# B611B.net
KiCad netlist of a schematic drawn in EAGLE
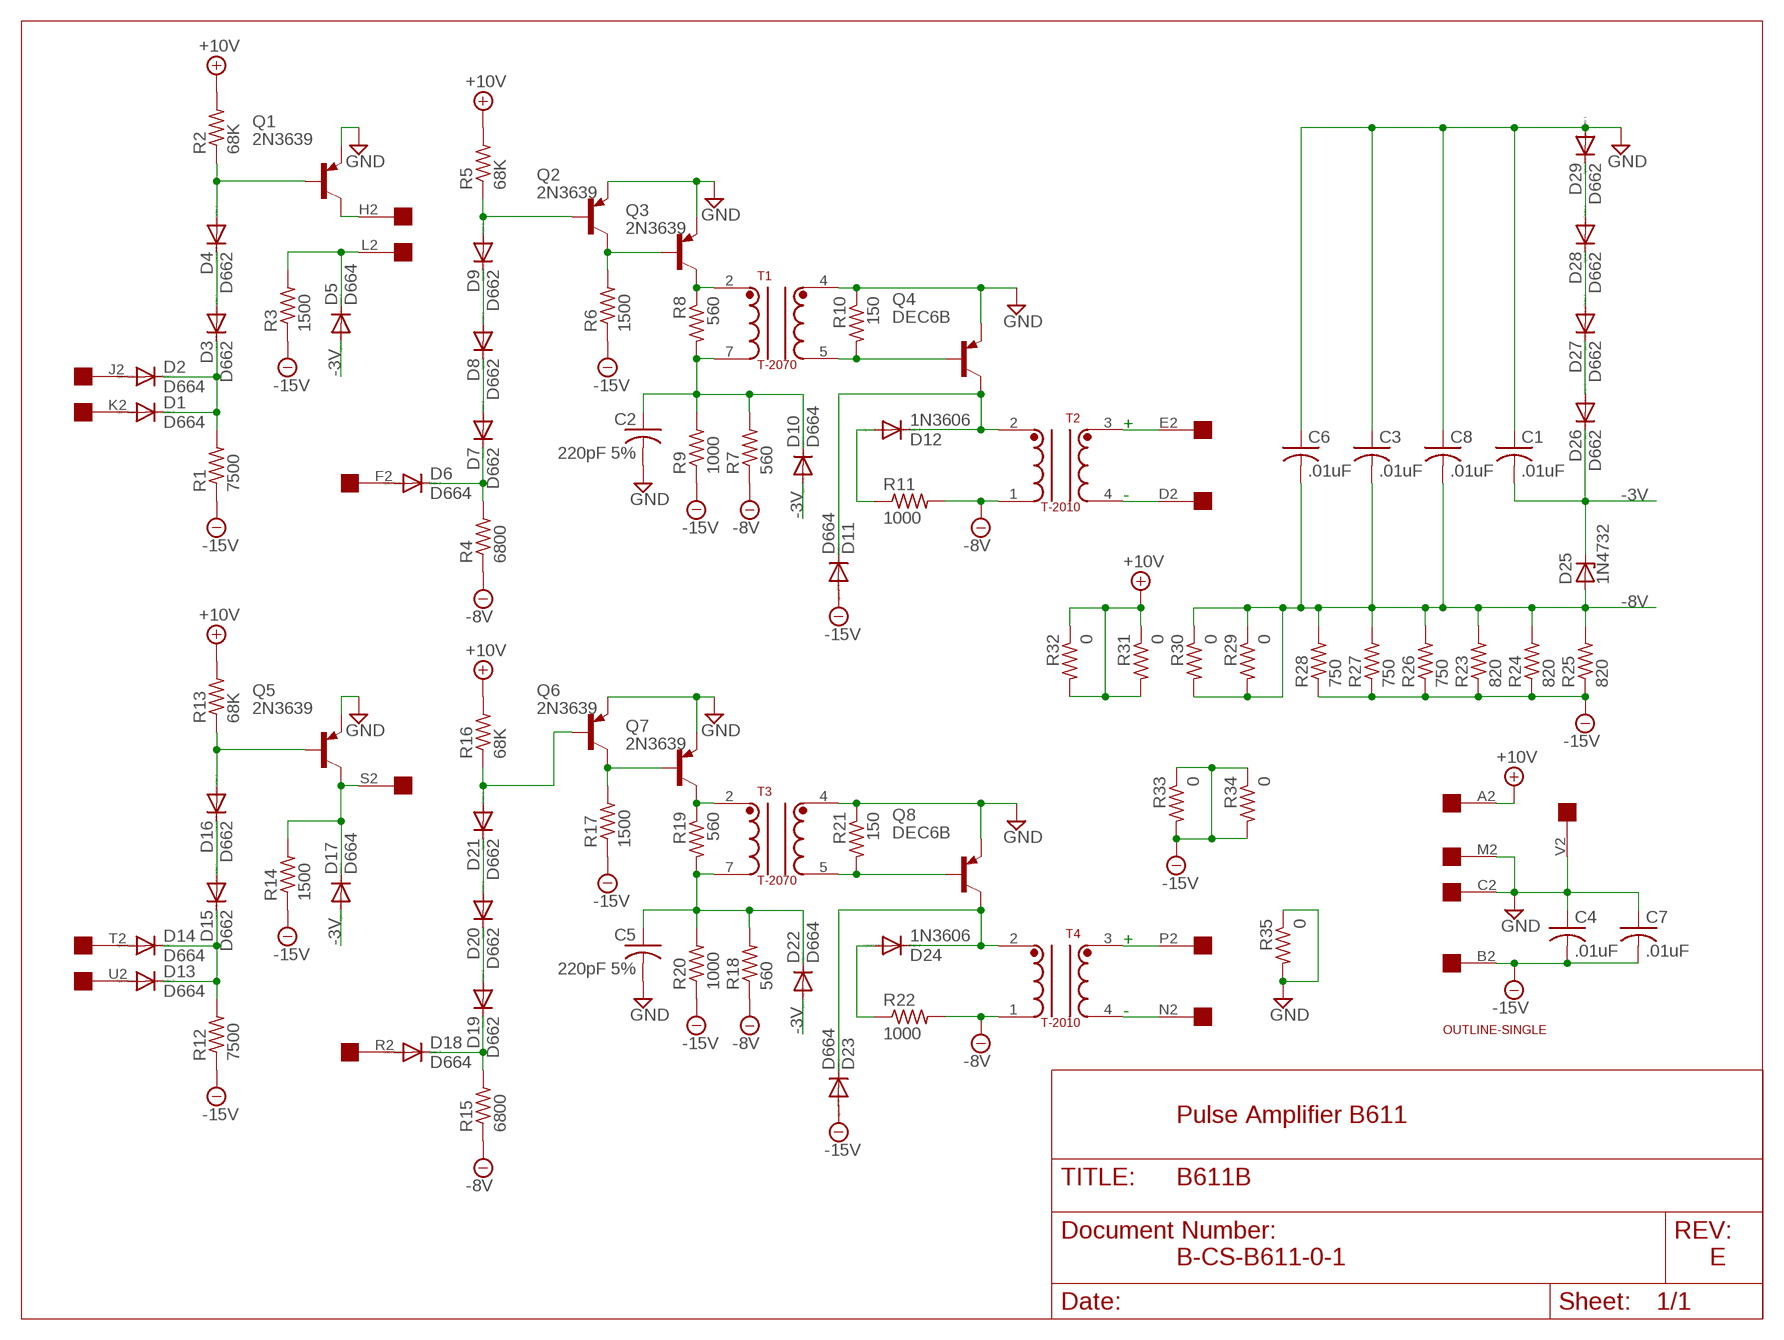
[diagram p0: schematic, sheet 1]

(export (version "E")
  (design (tool "Eeschema 10.0.6"))
  (components
    (comp (ref "C1")
      (value ".01uF")
      (footprint "eagle-import:C063-025X075")
      (libsource (lib "eagle-import") (part "C-US"))
    )
    (comp (ref "C2")
      (value "220pF 5%")
      (footprint "eagle-import:C150-054X183")
      (libsource (lib "eagle-import") (part "C-US150-054X183"))
    )
    (comp (ref "C3")
      (value ".01uF")
      (footprint "eagle-import:C063-025X075")
      (libsource (lib "eagle-import") (part "C-US"))
    )
    (comp (ref "C4")
      (value ".01uF")
      (footprint "eagle-import:C063-025X075")
      (libsource (lib "eagle-import") (part "C-US"))
    )
    (comp (ref "C5")
      (value "220pF 5%")
      (footprint "eagle-import:C150-054X183")
      (libsource (lib "eagle-import") (part "C-US150-054X183"))
    )
    (comp (ref "C6")
      (value ".01uF")
      (footprint "eagle-import:C063-025X075")
      (libsource (lib "eagle-import") (part "C-US"))
    )
    (comp (ref "C7")
      (value ".01uF")
      (footprint "eagle-import:C063-025X075")
      (libsource (lib "eagle-import") (part "C-US"))
    )
    (comp (ref "C8")
      (value ".01uF")
      (footprint "eagle-import:C063-025X075")
      (libsource (lib "eagle-import") (part "C-US"))
    )
    (comp (ref "D1")
      (value "D664")
      (footprint "eagle-import:DO35-10")
      (libsource (lib "eagle-import") (part "1N4148DO35-10"))
    )
    (comp (ref "D2")
      (value "D664")
      (footprint "eagle-import:DO35-10")
      (libsource (lib "eagle-import") (part "1N4148DO35-10"))
    )
    (comp (ref "D3")
      (value "D662")
      (footprint "eagle-import:DO35-10")
      (libsource (lib "eagle-import") (part "1N4148DO35-10"))
    )
    (comp (ref "D4")
      (value "D662")
      (footprint "eagle-import:DO35-10")
      (libsource (lib "eagle-import") (part "1N4148DO35-10"))
    )
    (comp (ref "D5")
      (value "D664")
      (footprint "eagle-import:DO35-10")
      (libsource (lib "eagle-import") (part "1N4148DO35-10"))
    )
    (comp (ref "D6")
      (value "D664")
      (footprint "eagle-import:DO35-10")
      (libsource (lib "eagle-import") (part "1N4148DO35-10"))
    )
    (comp (ref "D7")
      (value "D662")
      (footprint "eagle-import:DO35-10")
      (libsource (lib "eagle-import") (part "1N4148DO35-10"))
    )
    (comp (ref "D8")
      (value "D662")
      (footprint "eagle-import:DO35-10")
      (libsource (lib "eagle-import") (part "1N4148DO35-10"))
    )
    (comp (ref "D9")
      (value "D662")
      (footprint "eagle-import:DO35-10")
      (libsource (lib "eagle-import") (part "1N4148DO35-10"))
    )
    (comp (ref "D10")
      (value "D664")
      (footprint "eagle-import:DO35-10")
      (libsource (lib "eagle-import") (part "1N4148DO35-10"))
    )
    (comp (ref "D11")
      (value "D664")
      (footprint "eagle-import:DO35-10")
      (libsource (lib "eagle-import") (part "1N4148DO35-10"))
    )
    (comp (ref "D12")
      (value "1N3606")
      (footprint "eagle-import:DO35-10")
      (libsource (lib "eagle-import") (part "1N4148DO35-10"))
    )
    (comp (ref "D13")
      (value "D664")
      (footprint "eagle-import:DO35-10")
      (libsource (lib "eagle-import") (part "1N4148DO35-10"))
    )
    (comp (ref "D14")
      (value "D664")
      (footprint "eagle-import:DO35-10")
      (libsource (lib "eagle-import") (part "1N4148DO35-10"))
    )
    (comp (ref "D15")
      (value "D662")
      (footprint "eagle-import:DO35-10")
      (libsource (lib "eagle-import") (part "1N4148DO35-10"))
    )
    (comp (ref "D16")
      (value "D662")
      (footprint "eagle-import:DO35-10")
      (libsource (lib "eagle-import") (part "1N4148DO35-10"))
    )
    (comp (ref "D17")
      (value "D664")
      (footprint "eagle-import:DO35-10")
      (libsource (lib "eagle-import") (part "1N4148DO35-10"))
    )
    (comp (ref "D18")
      (value "D664")
      (footprint "eagle-import:DO35-10")
      (libsource (lib "eagle-import") (part "1N4148DO35-10"))
    )
    (comp (ref "D19")
      (value "D662")
      (footprint "eagle-import:DO35-10")
      (libsource (lib "eagle-import") (part "1N4148DO35-10"))
    )
    (comp (ref "D20")
      (value "D662")
      (footprint "eagle-import:DO35-10")
      (libsource (lib "eagle-import") (part "1N4148DO35-10"))
    )
    (comp (ref "D21")
      (value "D662")
      (footprint "eagle-import:DO35-10")
      (libsource (lib "eagle-import") (part "1N4148DO35-10"))
    )
    (comp (ref "D22")
      (value "D664")
      (footprint "eagle-import:DO35-10")
      (libsource (lib "eagle-import") (part "1N4148DO35-10"))
    )
    (comp (ref "D23")
      (value "D664")
      (footprint "eagle-import:DO35-10")
      (libsource (lib "eagle-import") (part "1N4148DO35-10"))
    )
    (comp (ref "D24")
      (value "1N3606")
      (footprint "eagle-import:DO35-10")
      (libsource (lib "eagle-import") (part "1N4148DO35-10"))
    )
    (comp (ref "D25")
      (value "1N4732")
      (footprint "eagle-import:DO35Z10")
      (libsource (lib "eagle-import") (part "ZENER-DIODEDO35Z10"))
    )
    (comp (ref "D26")
      (value "D662")
      (footprint "eagle-import:DO35-10")
      (libsource (lib "eagle-import") (part "1N4148DO35-10"))
    )
    (comp (ref "D27")
      (value "D662")
      (footprint "eagle-import:DO35-10")
      (libsource (lib "eagle-import") (part "1N4148DO35-10"))
    )
    (comp (ref "D28")
      (value "D662")
      (footprint "eagle-import:DO35-10")
      (libsource (lib "eagle-import") (part "1N4148DO35-10"))
    )
    (comp (ref "D29")
      (value "D662")
      (footprint "eagle-import:DO35-10")
      (libsource (lib "eagle-import") (part "1N4148DO35-10"))
    )
    (comp (ref "Q1")
      (value "2N3639")
      (footprint "eagle-import:TO39")
      (libsource (lib "eagle-import") (part "2N2904"))
    )
    (comp (ref "Q2")
      (value "2N3639")
      (footprint "eagle-import:TO39")
      (libsource (lib "eagle-import") (part "2N2904"))
    )
    (comp (ref "Q3")
      (value "2N3639")
      (footprint "eagle-import:TO39")
      (libsource (lib "eagle-import") (part "2N2904"))
    )
    (comp (ref "Q4")
      (value "DEC6B")
      (footprint "eagle-import:TO39")
      (libsource (lib "eagle-import") (part "2N2904"))
    )
    (comp (ref "Q5")
      (value "2N3639")
      (footprint "eagle-import:TO39")
      (libsource (lib "eagle-import") (part "2N2904"))
    )
    (comp (ref "Q6")
      (value "2N3639")
      (footprint "eagle-import:TO39")
      (libsource (lib "eagle-import") (part "2N2904"))
    )
    (comp (ref "Q7")
      (value "2N3639")
      (footprint "eagle-import:TO39")
      (libsource (lib "eagle-import") (part "2N2904"))
    )
    (comp (ref "Q8")
      (value "DEC6B")
      (footprint "eagle-import:TO39")
      (libsource (lib "eagle-import") (part "2N2904"))
    )
    (comp (ref "R1")
      (value "7500")
      (footprint "eagle-import:0207_10")
      (libsource (lib "eagle-import") (part "R-US_0207/10"))
    )
    (comp (ref "R2")
      (value "68K")
      (footprint "eagle-import:0207_10")
      (libsource (lib "eagle-import") (part "R-US_0207/10"))
    )
    (comp (ref "R3")
      (value "1500")
      (footprint "eagle-import:0207_10")
      (libsource (lib "eagle-import") (part "R-US_0207/10"))
    )
    (comp (ref "R4")
      (value "6800")
      (footprint "eagle-import:0207_10")
      (libsource (lib "eagle-import") (part "R-US_0207/10"))
    )
    (comp (ref "R5")
      (value "68K")
      (footprint "eagle-import:0207_10")
      (libsource (lib "eagle-import") (part "R-US_0207/10"))
    )
    (comp (ref "R6")
      (value "1500")
      (footprint "eagle-import:0207_10")
      (libsource (lib "eagle-import") (part "R-US_0207/10"))
    )
    (comp (ref "R7")
      (value "560")
      (footprint "eagle-import:0207_10")
      (libsource (lib "eagle-import") (part "R-US_0207/10"))
    )
    (comp (ref "R8")
      (value "560")
      (footprint "eagle-import:0207_10")
      (libsource (lib "eagle-import") (part "R-US_0207/10"))
    )
    (comp (ref "R9")
      (value "1000")
      (footprint "eagle-import:0207_10")
      (libsource (lib "eagle-import") (part "R-US_0207/10"))
    )
    (comp (ref "R10")
      (value "150")
      (footprint "eagle-import:0207_10")
      (libsource (lib "eagle-import") (part "R-US_0207/10"))
    )
    (comp (ref "R11")
      (value "1000")
      (footprint "eagle-import:0207_10")
      (libsource (lib "eagle-import") (part "R-US_0207/10"))
    )
    (comp (ref "R12")
      (value "7500")
      (footprint "eagle-import:0207_10")
      (libsource (lib "eagle-import") (part "R-US_0207/10"))
    )
    (comp (ref "R13")
      (value "68K")
      (footprint "eagle-import:0207_10")
      (libsource (lib "eagle-import") (part "R-US_0207/10"))
    )
    (comp (ref "R14")
      (value "1500")
      (footprint "eagle-import:0207_10")
      (libsource (lib "eagle-import") (part "R-US_0207/10"))
    )
    (comp (ref "R15")
      (value "6800")
      (footprint "eagle-import:0207_10")
      (libsource (lib "eagle-import") (part "R-US_0207/10"))
    )
    (comp (ref "R16")
      (value "68K")
      (footprint "eagle-import:0207_10")
      (libsource (lib "eagle-import") (part "R-US_0207/10"))
    )
    (comp (ref "R17")
      (value "1500")
      (footprint "eagle-import:0207_10")
      (libsource (lib "eagle-import") (part "R-US_0207/10"))
    )
    (comp (ref "R18")
      (value "560")
      (footprint "eagle-import:0207_10")
      (libsource (lib "eagle-import") (part "R-US_0207/10"))
    )
    (comp (ref "R19")
      (value "560")
      (footprint "eagle-import:0207_10")
      (libsource (lib "eagle-import") (part "R-US_0207/10"))
    )
    (comp (ref "R20")
      (value "1000")
      (footprint "eagle-import:0207_10")
      (libsource (lib "eagle-import") (part "R-US_0207/10"))
    )
    (comp (ref "R21")
      (value "150")
      (footprint "eagle-import:0207_10")
      (libsource (lib "eagle-import") (part "R-US_0207/10"))
    )
    (comp (ref "R22")
      (value "1000")
      (footprint "eagle-import:0207_10")
      (libsource (lib "eagle-import") (part "R-US_0207/10"))
    )
    (comp (ref "R23")
      (value "820")
      (footprint "eagle-import:0207_10")
      (libsource (lib "eagle-import") (part "R-US_0207/10"))
    )
    (comp (ref "R24")
      (value "820")
      (footprint "eagle-import:0207_10")
      (libsource (lib "eagle-import") (part "R-US_0207/10"))
    )
    (comp (ref "R25")
      (value "820")
      (footprint "eagle-import:0207_10")
      (libsource (lib "eagle-import") (part "R-US_0207/10"))
    )
    (comp (ref "R26")
      (value "750")
      (footprint "eagle-import:0207_10")
      (libsource (lib "eagle-import") (part "R-US_0207/10"))
    )
    (comp (ref "R27")
      (value "750")
      (footprint "eagle-import:0207_10")
      (libsource (lib "eagle-import") (part "R-US_0207/10"))
    )
    (comp (ref "R28")
      (value "750")
      (footprint "eagle-import:0207_10")
      (libsource (lib "eagle-import") (part "R-US_0207/10"))
    )
    (comp (ref "R29")
      (value "0")
      (footprint "eagle-import:0207_10")
      (libsource (lib "eagle-import") (part "R-US_0207/10"))
    )
    (comp (ref "R30")
      (value "0")
      (footprint "eagle-import:0207_10")
      (libsource (lib "eagle-import") (part "R-US_0207/10"))
    )
    (comp (ref "R31")
      (value "0")
      (footprint "eagle-import:0207_10")
      (libsource (lib "eagle-import") (part "R-US_0207/10"))
    )
    (comp (ref "R32")
      (value "0")
      (footprint "eagle-import:0207_10")
      (libsource (lib "eagle-import") (part "R-US_0207/10"))
    )
    (comp (ref "R33")
      (value "0")
      (footprint "eagle-import:0207_10")
      (libsource (lib "eagle-import") (part "R-US_0207/10"))
    )
    (comp (ref "R34")
      (value "0")
      (footprint "eagle-import:0207_10")
      (libsource (lib "eagle-import") (part "R-US_0207/10"))
    )
    (comp (ref "R35")
      (value "0")
      (footprint "eagle-import:0207_10")
      (libsource (lib "eagle-import") (part "R-US_0207/10"))
    )
    (comp (ref "T1")
      (value "T-2070")
      (footprint "eagle-import:TRANSFORMER")
      (libsource (lib "eagle-import") (part "T-2037"))
    )
    (comp (ref "T2")
      (value "T-2010")
      (footprint "eagle-import:TRANSFORMER2")
      (libsource (lib "eagle-import") (part "T-2010"))
    )
    (comp (ref "T3")
      (value "T-2070")
      (footprint "eagle-import:TRANSFORMER")
      (libsource (lib "eagle-import") (part "T-2037"))
    )
    (comp (ref "T4")
      (value "T-2010")
      (footprint "eagle-import:TRANSFORMER2")
      (libsource (lib "eagle-import") (part "T-2010"))
    )
    (comp (ref "U$1")
      (value "OUTLINE-SINGLE")
      (footprint "eagle-import:SINGLE")
      (libsource (lib "eagle-import") (part "OUTLINE-SINGLE"))
    )
    (comp (ref "U$2")
      (value "EDGE-1")
      (footprint "eagle-import:EDGE-CON1")
      (libsource (lib "eagle-import") (part "EDGE-1"))
    )
  )
  (nets
    (net (code "1") (name "+10V") (class "Default")
      (node (ref "R13") (pin "2") (pinfunction "2_2") (pintype "passive"))
      (node (ref "R16") (pin "2") (pinfunction "2_2") (pintype "passive"))
      (node (ref "R2") (pin "2") (pinfunction "2_2") (pintype "passive"))
      (node (ref "R31") (pin "1") (pinfunction "1_1") (pintype "passive"))
      (node (ref "R31") (pin "2") (pinfunction "2_2") (pintype "passive"))
      (node (ref "R32") (pin "1") (pinfunction "1_1") (pintype "passive"))
      (node (ref "R32") (pin "2") (pinfunction "2_2") (pintype "passive"))
      (node (ref "R5") (pin "2") (pinfunction "2_2") (pintype "passive"))
      (node (ref "U$2") (pin "A2") (pinfunction "1_A2") (pintype "bidirectional"))
    )
    (net (code "2") (name "-8V") (class "Default")
      (node (ref "C3") (pin "2") (pinfunction "2_2") (pintype "passive"))
      (node (ref "C6") (pin "2") (pinfunction "2_2") (pintype "passive"))
      (node (ref "C8") (pin "2") (pinfunction "2_2") (pintype "passive"))
      (node (ref "D25") (pin "A") (pinfunction "A_A") (pintype "passive"))
      (node (ref "R11") (pin "2") (pinfunction "2_2") (pintype "passive"))
      (node (ref "R15") (pin "1") (pinfunction "1_1") (pintype "passive"))
      (node (ref "R18") (pin "1") (pinfunction "1_1") (pintype "passive"))
      (node (ref "R22") (pin "2") (pinfunction "2_2") (pintype "passive"))
      (node (ref "R23") (pin "2") (pinfunction "2_2") (pintype "passive"))
      (node (ref "R24") (pin "2") (pinfunction "2_2") (pintype "passive"))
      (node (ref "R25") (pin "2") (pinfunction "2_2") (pintype "passive"))
      (node (ref "R26") (pin "2") (pinfunction "2_2") (pintype "passive"))
      (node (ref "R27") (pin "2") (pinfunction "2_2") (pintype "passive"))
      (node (ref "R28") (pin "2") (pinfunction "2_2") (pintype "passive"))
      (node (ref "R29") (pin "1") (pinfunction "1_1") (pintype "passive"))
      (node (ref "R29") (pin "2") (pinfunction "2_2") (pintype "passive"))
      (node (ref "R30") (pin "1") (pinfunction "1_1") (pintype "passive"))
      (node (ref "R30") (pin "2") (pinfunction "2_2") (pintype "passive"))
      (node (ref "R4") (pin "1") (pinfunction "1_1") (pintype "passive"))
      (node (ref "R7") (pin "1") (pinfunction "1_1") (pintype "passive"))
      (node (ref "T2") (pin "1") (pinfunction "P$5_1") (pintype "passive"))
      (node (ref "T4") (pin "1") (pinfunction "P$5_1") (pintype "passive"))
    )
    (net (code "3") (name "-15V") (class "Default")
      (node (ref "C4") (pin "2") (pinfunction "2_2") (pintype "passive"))
      (node (ref "C7") (pin "2") (pinfunction "2_2") (pintype "passive"))
      (node (ref "D11") (pin "A") (pinfunction "A_A") (pintype "passive"))
      (node (ref "D23") (pin "A") (pinfunction "A_A") (pintype "passive"))
      (node (ref "R1") (pin "1") (pinfunction "1_1") (pintype "passive"))
      (node (ref "R12") (pin "1") (pinfunction "1_1") (pintype "passive"))
      (node (ref "R14") (pin "1") (pinfunction "1_1") (pintype "passive"))
      (node (ref "R17") (pin "1") (pinfunction "1_1") (pintype "passive"))
      (node (ref "R20") (pin "1") (pinfunction "1_1") (pintype "passive"))
      (node (ref "R23") (pin "1") (pinfunction "1_1") (pintype "passive"))
      (node (ref "R24") (pin "1") (pinfunction "1_1") (pintype "passive"))
      (node (ref "R25") (pin "1") (pinfunction "1_1") (pintype "passive"))
      (node (ref "R26") (pin "1") (pinfunction "1_1") (pintype "passive"))
      (node (ref "R27") (pin "1") (pinfunction "1_1") (pintype "passive"))
      (node (ref "R28") (pin "1") (pinfunction "1_1") (pintype "passive"))
      (node (ref "R3") (pin "1") (pinfunction "1_1") (pintype "passive"))
      (node (ref "R33") (pin "1") (pinfunction "1_1") (pintype "passive"))
      (node (ref "R33") (pin "2") (pinfunction "2_2") (pintype "passive"))
      (node (ref "R34") (pin "1") (pinfunction "1_1") (pintype "passive"))
      (node (ref "R34") (pin "2") (pinfunction "2_2") (pintype "passive"))
      (node (ref "R6") (pin "1") (pinfunction "1_1") (pintype "passive"))
      (node (ref "R9") (pin "1") (pinfunction "1_1") (pintype "passive"))
      (node (ref "U$2") (pin "B2") (pinfunction "1_B2") (pintype "bidirectional"))
    )
    (net (code "4") (name "/-3V") (class "Default")
      (node (ref "C1") (pin "2") (pinfunction "2_2") (pintype "passive"))
      (node (ref "D10") (pin "A") (pinfunction "A_A") (pintype "passive"))
      (node (ref "D17") (pin "A") (pinfunction "A_A") (pintype "passive"))
      (node (ref "D22") (pin "A") (pinfunction "A_A") (pintype "passive"))
      (node (ref "D25") (pin "C") (pinfunction "C_C") (pintype "passive"))
      (node (ref "D26") (pin "C") (pinfunction "C_C") (pintype "passive"))
      (node (ref "D5") (pin "A") (pinfunction "A_A") (pintype "passive"))
    )
    (net (code "5") (name "GND") (class "Default")
      (node (ref "C1") (pin "1") (pinfunction "1_1") (pintype "passive"))
      (node (ref "C2") (pin "2") (pinfunction "2_2") (pintype "passive"))
      (node (ref "C3") (pin "1") (pinfunction "1_1") (pintype "passive"))
      (node (ref "C4") (pin "1") (pinfunction "1_1") (pintype "passive"))
      (node (ref "C5") (pin "2") (pinfunction "2_2") (pintype "passive"))
      (node (ref "C6") (pin "1") (pinfunction "1_1") (pintype "passive"))
      (node (ref "C7") (pin "1") (pinfunction "1_1") (pintype "passive"))
      (node (ref "C8") (pin "1") (pinfunction "1_1") (pintype "passive"))
      (node (ref "D29") (pin "A") (pinfunction "A_A") (pintype "passive"))
      (node (ref "Q1") (pin "1") (pinfunction "E_1") (pintype "passive"))
      (node (ref "Q2") (pin "1") (pinfunction "E_1") (pintype "passive"))
      (node (ref "Q3") (pin "1") (pinfunction "E_1") (pintype "passive"))
      (node (ref "Q4") (pin "1") (pinfunction "E_1") (pintype "passive"))
      (node (ref "Q5") (pin "1") (pinfunction "E_1") (pintype "passive"))
      (node (ref "Q6") (pin "1") (pinfunction "E_1") (pintype "passive"))
      (node (ref "Q7") (pin "1") (pinfunction "E_1") (pintype "passive"))
      (node (ref "Q8") (pin "1") (pinfunction "E_1") (pintype "passive"))
      (node (ref "R10") (pin "1") (pinfunction "1_1") (pintype "passive"))
      (node (ref "R21") (pin "1") (pinfunction "1_1") (pintype "passive"))
      (node (ref "R35") (pin "1") (pinfunction "1_1") (pintype "passive"))
      (node (ref "R35") (pin "2") (pinfunction "2_2") (pintype "passive"))
      (node (ref "T1") (pin "4") (pinfunction "P$4_4") (pintype "passive"))
      (node (ref "T3") (pin "4") (pinfunction "P$4_4") (pintype "passive"))
      (node (ref "U$2") (pin "C2") (pinfunction "1_C2") (pintype "bidirectional"))
      (node (ref "U$2") (pin "M2") (pinfunction "1_M2") (pintype "bidirectional"))
      (node (ref "U$2") (pin "V2") (pinfunction "1_V2") (pintype "bidirectional"))
    )
    (net (code "6") (name "Net-(D1-PadC)") (class "Default")
      (node (ref "D1") (pin "C") (pinfunction "C_C") (pintype "passive"))
      (node (ref "D2") (pin "C") (pinfunction "C_C") (pintype "passive"))
      (node (ref "D3") (pin "C") (pinfunction "C_C") (pintype "passive"))
      (node (ref "R1") (pin "2") (pinfunction "2_2") (pintype "passive"))
    )
    (net (code "7") (name "Net-(D3-PadA)") (class "Default")
      (node (ref "D3") (pin "A") (pinfunction "A_A") (pintype "passive"))
      (node (ref "D4") (pin "C") (pinfunction "C_C") (pintype "passive"))
    )
    (net (code "8") (name "Net-(D6-PadC)") (class "Default")
      (node (ref "D6") (pin "C") (pinfunction "C_C") (pintype "passive"))
      (node (ref "D7") (pin "C") (pinfunction "C_C") (pintype "passive"))
      (node (ref "R4") (pin "2") (pinfunction "2_2") (pintype "passive"))
    )
    (net (code "9") (name "Net-(D7-PadA)") (class "Default")
      (node (ref "D7") (pin "A") (pinfunction "A_A") (pintype "passive"))
      (node (ref "D8") (pin "C") (pinfunction "C_C") (pintype "passive"))
    )
    (net (code "10") (name "Net-(D8-PadA)") (class "Default")
      (node (ref "D8") (pin "A") (pinfunction "A_A") (pintype "passive"))
      (node (ref "D9") (pin "C") (pinfunction "C_C") (pintype "passive"))
    )
    (net (code "11") (name "Net-(D12-PadA)") (class "Default")
      (node (ref "D12") (pin "A") (pinfunction "A_A") (pintype "passive"))
      (node (ref "R11") (pin "1") (pinfunction "1_1") (pintype "passive"))
    )
    (net (code "12") (name "Net-(D13-PadC)") (class "Default")
      (node (ref "D13") (pin "C") (pinfunction "C_C") (pintype "passive"))
      (node (ref "D14") (pin "C") (pinfunction "C_C") (pintype "passive"))
      (node (ref "D15") (pin "C") (pinfunction "C_C") (pintype "passive"))
      (node (ref "R12") (pin "2") (pinfunction "2_2") (pintype "passive"))
    )
    (net (code "13") (name "Net-(D15-PadA)") (class "Default")
      (node (ref "D15") (pin "A") (pinfunction "A_A") (pintype "passive"))
      (node (ref "D16") (pin "C") (pinfunction "C_C") (pintype "passive"))
    )
    (net (code "14") (name "Net-(D18-PadC)") (class "Default")
      (node (ref "D18") (pin "C") (pinfunction "C_C") (pintype "passive"))
      (node (ref "D19") (pin "C") (pinfunction "C_C") (pintype "passive"))
      (node (ref "R15") (pin "2") (pinfunction "2_2") (pintype "passive"))
    )
    (net (code "15") (name "Net-(D19-PadA)") (class "Default")
      (node (ref "D19") (pin "A") (pinfunction "A_A") (pintype "passive"))
      (node (ref "D20") (pin "C") (pinfunction "C_C") (pintype "passive"))
    )
    (net (code "16") (name "Net-(D20-PadA)") (class "Default")
      (node (ref "D20") (pin "A") (pinfunction "A_A") (pintype "passive"))
      (node (ref "D21") (pin "C") (pinfunction "C_C") (pintype "passive"))
    )
    (net (code "17") (name "Net-(D24-PadA)") (class "Default")
      (node (ref "D24") (pin "A") (pinfunction "A_A") (pintype "passive"))
      (node (ref "R22") (pin "1") (pinfunction "1_1") (pintype "passive"))
    )
    (net (code "18") (name "Net-(D26-PadA)") (class "Default")
      (node (ref "D26") (pin "A") (pinfunction "A_A") (pintype "passive"))
      (node (ref "D27") (pin "C") (pinfunction "C_C") (pintype "passive"))
    )
    (net (code "19") (name "Net-(D27-PadA)") (class "Default")
      (node (ref "D27") (pin "A") (pinfunction "A_A") (pintype "passive"))
      (node (ref "D28") (pin "C") (pinfunction "C_C") (pintype "passive"))
    )
    (net (code "20") (name "Net-(D28-PadA)") (class "Default")
      (node (ref "D28") (pin "A") (pinfunction "A_A") (pintype "passive"))
      (node (ref "D29") (pin "C") (pinfunction "C_C") (pintype "passive"))
    )
    (net (code "21") (name "Net-(Q1-B)") (class "Default")
      (node (ref "D4") (pin "A") (pinfunction "A_A") (pintype "passive"))
      (node (ref "Q1") (pin "2") (pinfunction "B_2") (pintype "passive"))
      (node (ref "R2") (pin "1") (pinfunction "1_1") (pintype "passive"))
    )
    (net (code "22") (name "Net-(Q1-C)") (class "Default")
      (node (ref "Q1") (pin "3") (pinfunction "C_3") (pintype "passive"))
      (node (ref "U$2") (pin "H2") (pinfunction "1_H2") (pintype "bidirectional"))
    )
    (net (code "23") (name "Net-(Q2-B)") (class "Default")
      (node (ref "D9") (pin "A") (pinfunction "A_A") (pintype "passive"))
      (node (ref "Q2") (pin "2") (pinfunction "B_2") (pintype "passive"))
      (node (ref "R5") (pin "1") (pinfunction "1_1") (pintype "passive"))
    )
    (net (code "24") (name "Net-(Q2-C)") (class "Default")
      (node (ref "Q2") (pin "3") (pinfunction "C_3") (pintype "passive"))
      (node (ref "Q3") (pin "2") (pinfunction "B_2") (pintype "passive"))
      (node (ref "R6") (pin "2") (pinfunction "2_2") (pintype "passive"))
    )
    (net (code "25") (name "Net-(Q3-C)") (class "Default")
      (node (ref "Q3") (pin "3") (pinfunction "C_3") (pintype "passive"))
      (node (ref "R8") (pin "1") (pinfunction "1_1") (pintype "passive"))
      (node (ref "T1") (pin "2") (pinfunction "P$2_2") (pintype "passive"))
    )
    (net (code "26") (name "Net-(Q4-B)") (class "Default")
      (node (ref "Q4") (pin "2") (pinfunction "B_2") (pintype "passive"))
      (node (ref "R10") (pin "2") (pinfunction "2_2") (pintype "passive"))
      (node (ref "T1") (pin "5") (pinfunction "P$5_5") (pintype "passive"))
    )
    (net (code "27") (name "Net-(Q4-C)") (class "Default")
      (node (ref "D11") (pin "C") (pinfunction "C_C") (pintype "passive"))
      (node (ref "D12") (pin "C") (pinfunction "C_C") (pintype "passive"))
      (node (ref "Q4") (pin "3") (pinfunction "C_3") (pintype "passive"))
      (node (ref "T2") (pin "2") (pinfunction "P$4_2") (pintype "passive"))
    )
    (net (code "28") (name "Net-(Q5-B)") (class "Default")
      (node (ref "D16") (pin "A") (pinfunction "A_A") (pintype "passive"))
      (node (ref "Q5") (pin "2") (pinfunction "B_2") (pintype "passive"))
      (node (ref "R13") (pin "1") (pinfunction "1_1") (pintype "passive"))
    )
    (net (code "29") (name "Net-(Q5-C)") (class "Default")
      (node (ref "D17") (pin "C") (pinfunction "C_C") (pintype "passive"))
      (node (ref "Q5") (pin "3") (pinfunction "C_3") (pintype "passive"))
      (node (ref "R14") (pin "2") (pinfunction "2_2") (pintype "passive"))
      (node (ref "U$2") (pin "S2") (pinfunction "1_S2") (pintype "bidirectional"))
    )
    (net (code "30") (name "Net-(Q6-B)") (class "Default")
      (node (ref "D21") (pin "A") (pinfunction "A_A") (pintype "passive"))
      (node (ref "Q6") (pin "2") (pinfunction "B_2") (pintype "passive"))
      (node (ref "R16") (pin "1") (pinfunction "1_1") (pintype "passive"))
    )
    (net (code "31") (name "Net-(Q6-C)") (class "Default")
      (node (ref "Q6") (pin "3") (pinfunction "C_3") (pintype "passive"))
      (node (ref "Q7") (pin "2") (pinfunction "B_2") (pintype "passive"))
      (node (ref "R17") (pin "2") (pinfunction "2_2") (pintype "passive"))
    )
    (net (code "32") (name "Net-(Q7-C)") (class "Default")
      (node (ref "Q7") (pin "3") (pinfunction "C_3") (pintype "passive"))
      (node (ref "R19") (pin "1") (pinfunction "1_1") (pintype "passive"))
      (node (ref "T3") (pin "2") (pinfunction "P$2_2") (pintype "passive"))
    )
    (net (code "33") (name "Net-(Q8-B)") (class "Default")
      (node (ref "Q8") (pin "2") (pinfunction "B_2") (pintype "passive"))
      (node (ref "R21") (pin "2") (pinfunction "2_2") (pintype "passive"))
      (node (ref "T3") (pin "5") (pinfunction "P$5_5") (pintype "passive"))
    )
    (net (code "34") (name "Net-(Q8-C)") (class "Default")
      (node (ref "D23") (pin "C") (pinfunction "C_C") (pintype "passive"))
      (node (ref "D24") (pin "C") (pinfunction "C_C") (pintype "passive"))
      (node (ref "Q8") (pin "3") (pinfunction "C_3") (pintype "passive"))
      (node (ref "T4") (pin "2") (pinfunction "P$4_2") (pintype "passive"))
    )
    (net (code "35") (name "Net-(T1-P$7)") (class "Default")
      (node (ref "C2") (pin "1") (pinfunction "1_1") (pintype "passive"))
      (node (ref "D10") (pin "C") (pinfunction "C_C") (pintype "passive"))
      (node (ref "R7") (pin "2") (pinfunction "2_2") (pintype "passive"))
      (node (ref "R8") (pin "2") (pinfunction "2_2") (pintype "passive"))
      (node (ref "R9") (pin "2") (pinfunction "2_2") (pintype "passive"))
      (node (ref "T1") (pin "7") (pinfunction "P$7_7") (pintype "passive"))
    )
    (net (code "36") (name "Net-(T2-P$2)") (class "Default")
      (node (ref "T2") (pin "3") (pinfunction "P$2_3") (pintype "passive"))
      (node (ref "U$2") (pin "E2") (pinfunction "1_E2") (pintype "bidirectional"))
    )
    (net (code "37") (name "Net-(T2-P$7)") (class "Default")
      (node (ref "T2") (pin "4") (pinfunction "P$7_4") (pintype "passive"))
      (node (ref "U$2") (pin "D2") (pinfunction "1_D2") (pintype "bidirectional"))
    )
    (net (code "38") (name "Net-(T3-P$7)") (class "Default")
      (node (ref "C5") (pin "1") (pinfunction "1_1") (pintype "passive"))
      (node (ref "D22") (pin "C") (pinfunction "C_C") (pintype "passive"))
      (node (ref "R18") (pin "2") (pinfunction "2_2") (pintype "passive"))
      (node (ref "R19") (pin "2") (pinfunction "2_2") (pintype "passive"))
      (node (ref "R20") (pin "2") (pinfunction "2_2") (pintype "passive"))
      (node (ref "T3") (pin "7") (pinfunction "P$7_7") (pintype "passive"))
    )
    (net (code "39") (name "Net-(T4-P$2)") (class "Default")
      (node (ref "T4") (pin "3") (pinfunction "P$2_3") (pintype "passive"))
      (node (ref "U$2") (pin "P2") (pinfunction "1_P2") (pintype "bidirectional"))
    )
    (net (code "40") (name "Net-(T4-P$7)") (class "Default")
      (node (ref "T4") (pin "4") (pinfunction "P$7_4") (pintype "passive"))
      (node (ref "U$2") (pin "N2") (pinfunction "1_N2") (pintype "bidirectional"))
    )
    (net (code "41") (name "Net-(U$2F-1)") (class "Default")
      (node (ref "D6") (pin "A") (pinfunction "A_A") (pintype "passive"))
      (node (ref "U$2") (pin "F2") (pinfunction "1_F2") (pintype "bidirectional"))
    )
    (net (code "42") (name "Net-(U$2H-1)") (class "Default")
      (node (ref "D2") (pin "A") (pinfunction "A_A") (pintype "passive"))
      (node (ref "U$2") (pin "J2") (pinfunction "1_J2") (pintype "bidirectional"))
    )
    (net (code "43") (name "Net-(U$2I-1)") (class "Default")
      (node (ref "D1") (pin "A") (pinfunction "A_A") (pintype "passive"))
      (node (ref "U$2") (pin "K2") (pinfunction "1_K2") (pintype "bidirectional"))
    )
    (net (code "44") (name "Net-(U$2J-1)") (class "Default")
      (node (ref "D5") (pin "C") (pinfunction "C_C") (pintype "passive"))
      (node (ref "R3") (pin "2") (pinfunction "2_2") (pintype "passive"))
      (node (ref "U$2") (pin "L2") (pinfunction "1_L2") (pintype "bidirectional"))
    )
    (net (code "45") (name "Net-(U$2N-1)") (class "Default")
      (node (ref "D18") (pin "A") (pinfunction "A_A") (pintype "passive"))
      (node (ref "U$2") (pin "R2") (pinfunction "1_R2") (pintype "bidirectional"))
    )
    (net (code "46") (name "Net-(U$2P-1)") (class "Default")
      (node (ref "D14") (pin "A") (pinfunction "A_A") (pintype "passive"))
      (node (ref "U$2") (pin "T2") (pinfunction "1_T2") (pintype "bidirectional"))
    )
    (net (code "47") (name "Net-(U$2Q-1)") (class "Default")
      (node (ref "D13") (pin "A") (pinfunction "A_A") (pintype "passive"))
      (node (ref "U$2") (pin "U2") (pinfunction "1_U2") (pintype "bidirectional"))
    )
  )
)
